# vario_1.net
KiCad netlist of a schematic drawn in EAGLE
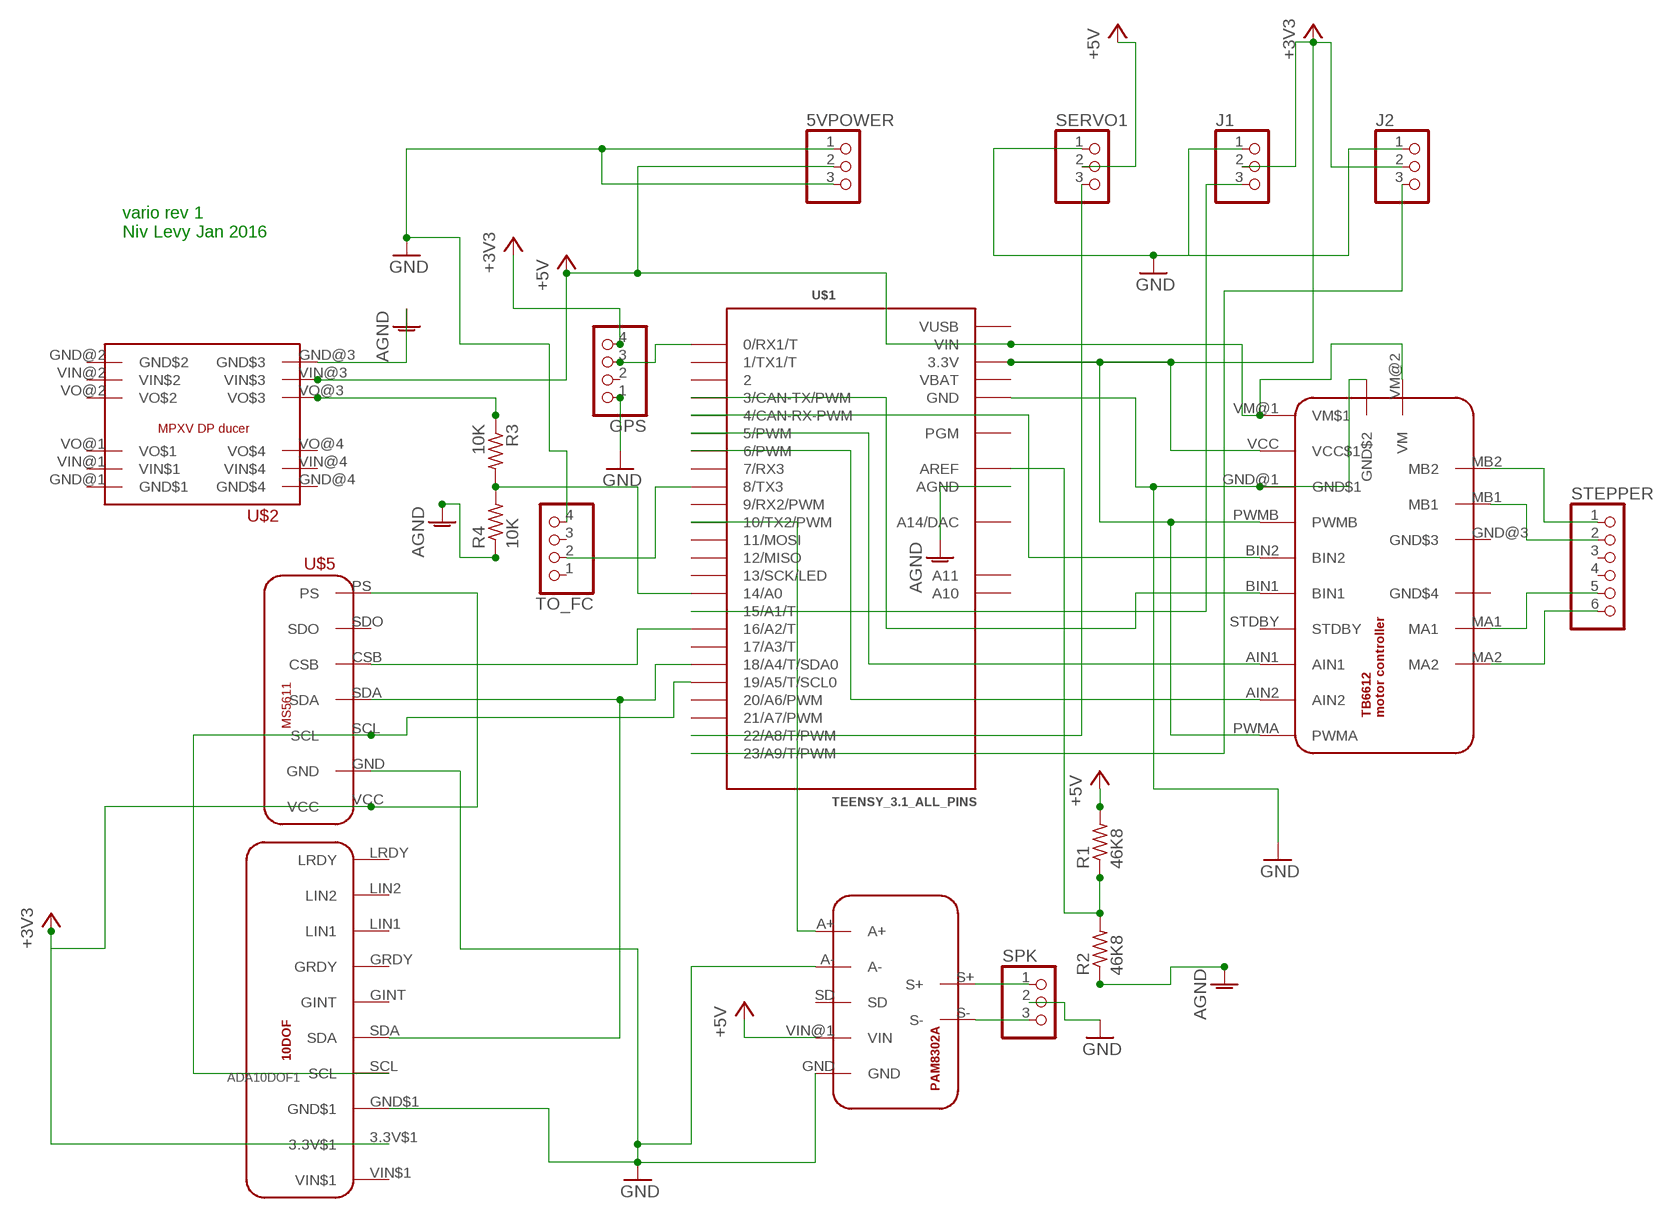
[diagram p0: schematic, sheet 1]

(export (version "E")
  (design (tool "Eeschema 10.0.6"))
  (components
    (comp (ref "5VPOWER")
      (value "PINHD-1X3")
      (footprint "eagle-import:1X03")
      (libsource (lib "eagle-import") (part "PINHD-1X3"))
    )
    (comp (ref "ADA10DOF1")
      (value "10DOF_BREAKOUT")
      (footprint "eagle-import:10_DOF_BREAKOUT")
      (libsource (lib "eagle-import") (part "10DOF_BREAKOUT"))
    )
    (comp (ref "GPS")
      (value "PINHD-1X4")
      (footprint "eagle-import:1X04")
      (libsource (lib "eagle-import") (part "PINHD-1X4"))
    )
    (comp (ref "J1")
      (value "PINHD-1X3")
      (footprint "eagle-import:1X03")
      (libsource (lib "eagle-import") (part "PINHD-1X3"))
    )
    (comp (ref "J2")
      (value "PINHD-1X3")
      (footprint "eagle-import:1X03")
      (libsource (lib "eagle-import") (part "PINHD-1X3"))
    )
    (comp (ref "R1")
      (value "46K8")
      (footprint "eagle-import:0207_10")
      (libsource (lib "eagle-import") (part "R-US_0207/10"))
    )
    (comp (ref "R2")
      (value "46K8")
      (footprint "eagle-import:0207_10")
      (libsource (lib "eagle-import") (part "R-US_0207/10"))
    )
    (comp (ref "R3")
      (value "10K")
      (footprint "eagle-import:0207_10")
      (libsource (lib "eagle-import") (part "R-US_0207/10"))
    )
    (comp (ref "R4")
      (value "10K")
      (footprint "eagle-import:0207_10")
      (libsource (lib "eagle-import") (part "R-US_0207/10"))
    )
    (comp (ref "SERVO1")
      (value "PINHD-1X3")
      (footprint "eagle-import:1X03")
      (libsource (lib "eagle-import") (part "PINHD-1X3"))
    )
    (comp (ref "SPK")
      (value "PINHD-1X3")
      (footprint "eagle-import:1X03")
      (libsource (lib "eagle-import") (part "PINHD-1X3"))
    )
    (comp (ref "STEPPER")
      (value "PINHD-1X6")
      (footprint "eagle-import:1X06")
      (libsource (lib "eagle-import") (part "PINHD-1X6"))
    )
    (comp (ref "TO_FC")
      (value "PINHD-1X4")
      (footprint "eagle-import:1X04")
      (libsource (lib "eagle-import") (part "PINHD-1X4"))
    )
    (comp (ref "U$1")
      (value "TEENSY_3.1_ALL_PINS")
      (footprint "eagle-import:TEENSY3-ALL_PINS")
      (libsource (lib "eagle-import") (part "TEENSY_3.1_ALL_PINS"))
    )
    (comp (ref "U$2")
      (value "MPXV")
      (footprint "eagle-import:MPXV")
      (libsource (lib "eagle-import") (part "MPXV"))
    )
    (comp (ref "U$3")
      (value "TB6612_BREAKOUT")
      (footprint "eagle-import:TB6612_BREAKOUT")
      (libsource (lib "eagle-import") (part "TB6612_BREAKOUT"))
    )
    (comp (ref "U$4")
      (value "PAM8302A_BREAKOUT")
      (footprint "eagle-import:PAM8302A_BREAKOUT")
      (libsource (lib "eagle-import") (part "PAM8302A_BREAKOUT"))
    )
    (comp (ref "U$5")
      (value "MS5611_BREAKOUT")
      (footprint "eagle-import:MS5611_BREAKOUT")
      (libsource (lib "eagle-import") (part "MS5611_BREAKOUT"))
    )
  )
  (nets
    (net (code "1") (name "+3V3") (class "Default")
      (node (ref "ADA10DOF1") (pin "3.3V$1") (pinfunction "3.3V$1_3.3V$1") (pintype "input"))
      (node (ref "GPS") (pin "4") (pinfunction "4_4") (pintype "passive"))
      (node (ref "J1") (pin "2") (pinfunction "2_2") (pintype "passive"))
      (node (ref "J2") (pin "2") (pinfunction "2_2") (pintype "passive"))
      (node (ref "U$1") (pin "3.3V") (pinfunction "3.3V_3.3V") (pintype "power_in"))
      (node (ref "U$1") (pin "3.3V1") (pinfunction "3.3V_3.3V1") (pintype "power_in"))
      (node (ref "U$3") (pin "PWMA") (pinfunction "PWMA_PWMA") (pintype "bidirectional"))
      (node (ref "U$3") (pin "PWMB") (pinfunction "PWMB_PWMB") (pintype "bidirectional"))
      (node (ref "U$3") (pin "VCC") (pinfunction "VCC$1_VCC") (pintype "input"))
      (node (ref "U$5") (pin "PS") (pinfunction "PS_PS") (pintype "bidirectional"))
      (node (ref "U$5") (pin "VCC") (pinfunction "VCC_VCC") (pintype "input"))
    )
    (net (code "2") (name "+5V") (class "Default")
      (node (ref "5VPOWER") (pin "2") (pinfunction "2_2") (pintype "passive"))
      (node (ref "R1") (pin "2") (pinfunction "2_2") (pintype "passive"))
      (node (ref "SERVO1") (pin "2") (pinfunction "2_2") (pintype "passive"))
      (node (ref "U$1") (pin "VIN") (pinfunction "VIN_VIN") (pintype "power_in"))
      (node (ref "U$2") (pin "VIN@3") (pinfunction "VIN$3_VIN@3") (pintype "input"))
      (node (ref "U$3") (pin "VM@1") (pinfunction "VM$1_VM@1") (pintype "input"))
      (node (ref "U$3") (pin "VM@2") (pinfunction "VM_VM@2") (pintype "bidirectional"))
      (node (ref "U$4") (pin "VIN@1") (pinfunction "VIN_VIN@1") (pintype "input"))
    )
    (net (code "3") (name "/VBAT") (class "Default")
      (node (ref "U$1") (pin "VBAT") (pinfunction "VBAT_VBAT") (pintype "power_in"))
    )
    (net (code "4") (name "/VUSB") (class "Default")
      (node (ref "U$1") (pin "VUSB") (pinfunction "VUSB_VUSB") (pintype "power_in"))
    )
    (net (code "5") (name "AGND") (class "Default")
      (node (ref "R2") (pin "1") (pinfunction "1_1") (pintype "passive"))
      (node (ref "R4") (pin "1") (pinfunction "1_1") (pintype "passive"))
      (node (ref "U$1") (pin "AGND") (pinfunction "AGND_AGND") (pintype "power_in"))
      (node (ref "U$2") (pin "GND@3") (pinfunction "GND$3_GND@3") (pintype "input"))
    )
    (net (code "6") (name "GND") (class "Default")
      (node (ref "5VPOWER") (pin "1") (pinfunction "1_1") (pintype "passive"))
      (node (ref "5VPOWER") (pin "3") (pinfunction "3_3") (pintype "passive"))
      (node (ref "ADA10DOF1") (pin "GND$1") (pinfunction "GND$1_GND$1") (pintype "input"))
      (node (ref "GPS") (pin "1") (pinfunction "1_1") (pintype "passive"))
      (node (ref "J1") (pin "1") (pinfunction "1_1") (pintype "passive"))
      (node (ref "J2") (pin "1") (pinfunction "1_1") (pintype "passive"))
      (node (ref "SERVO1") (pin "1") (pinfunction "1_1") (pintype "passive"))
      (node (ref "SPK") (pin "2") (pinfunction "2_2") (pintype "passive"))
      (node (ref "TO_FC") (pin "4") (pinfunction "4_4") (pintype "passive"))
      (node (ref "U$1") (pin "GND") (pinfunction "GND_GND") (pintype "power_in"))
      (node (ref "U$1") (pin "GND1") (pinfunction "GND_GND1") (pintype "power_in"))
      (node (ref "U$3") (pin "GND@1") (pinfunction "GND$1_GND@1") (pintype "input"))
      (node (ref "U$3") (pin "GND@2") (pinfunction "GND$2_GND@2") (pintype "input"))
      (node (ref "U$4") (pin "A-") (pinfunction "A-_A-") (pintype "bidirectional"))
      (node (ref "U$4") (pin "GND") (pinfunction "GND_GND") (pintype "input"))
      (node (ref "U$5") (pin "GND") (pinfunction "GND_GND") (pintype "bidirectional"))
    )
    (net (code "7") (name "Net-(R1-Pad1)") (class "Default")
      (node (ref "R1") (pin "1") (pinfunction "1_1") (pintype "passive"))
      (node (ref "R2") (pin "2") (pinfunction "2_2") (pintype "passive"))
      (node (ref "U$1") (pin "AREF") (pinfunction "AREF_AREF") (pintype "power_in"))
    )
    (net (code "8") (name "Net-(R3-Pad2)") (class "Default")
      (node (ref "R3") (pin "2") (pinfunction "2_2") (pintype "passive"))
      (node (ref "R4") (pin "2") (pinfunction "2_2") (pintype "passive"))
      (node (ref "U$1") (pin "14/A0") (pinfunction "14/A0_14/A0") (pintype "bidirectional"))
    )
    (net (code "9") (name "Net-(SPK-Pad1)") (class "Default")
      (node (ref "SPK") (pin "1") (pinfunction "1_1") (pintype "passive"))
      (node (ref "U$4") (pin "S+") (pinfunction "S+_S+") (pintype "bidirectional"))
    )
    (net (code "10") (name "Net-(SPK-Pad3)") (class "Default")
      (node (ref "SPK") (pin "3") (pinfunction "3_3") (pintype "passive"))
      (node (ref "U$4") (pin "S-") (pinfunction "S-_S-") (pintype "bidirectional"))
    )
    (net (code "11") (name "Net-(STEPPER-Pad1)") (class "Default")
      (node (ref "STEPPER") (pin "1") (pinfunction "1_1") (pintype "passive"))
      (node (ref "U$3") (pin "MB2") (pinfunction "MB2_MB2") (pintype "bidirectional"))
    )
    (net (code "12") (name "Net-(STEPPER-Pad2)") (class "Default")
      (node (ref "STEPPER") (pin "2") (pinfunction "2_2") (pintype "passive"))
      (node (ref "U$3") (pin "MB1") (pinfunction "MB1_MB1") (pintype "bidirectional"))
    )
    (net (code "13") (name "Net-(STEPPER-Pad5)") (class "Default")
      (node (ref "STEPPER") (pin "5") (pinfunction "5_5") (pintype "passive"))
      (node (ref "U$3") (pin "MA1") (pinfunction "MA1_MA1") (pintype "bidirectional"))
    )
    (net (code "14") (name "Net-(STEPPER-Pad6)") (class "Default")
      (node (ref "STEPPER") (pin "6") (pinfunction "6_6") (pintype "passive"))
      (node (ref "U$3") (pin "MA2") (pinfunction "MA2_MA2") (pintype "bidirectional"))
    )
    (net (code "15") (name "Net-(U$1-0{slash}RX1{slash}T)") (class "Default")
      (node (ref "GPS") (pin "3") (pinfunction "3_3") (pintype "passive"))
      (node (ref "U$1") (pin "0") (pinfunction "0/RX1/T_0") (pintype "bidirectional"))
    )
    (net (code "16") (name "Net-(U$1-3{slash}CAN-TX{slash}PWM)") (class "Default")
      (node (ref "U$1") (pin "3") (pinfunction "3/CAN-TX/PWM_3") (pintype "bidirectional"))
      (node (ref "U$3") (pin "BIN1") (pinfunction "BIN1_BIN1") (pintype "bidirectional"))
    )
    (net (code "17") (name "Net-(U$1-4{slash}CAN-RX-PWM)") (class "Default")
      (node (ref "U$1") (pin "4") (pinfunction "4/CAN-RX-PWM_4") (pintype "bidirectional"))
      (node (ref "U$3") (pin "BIN2") (pinfunction "BIN2_BIN2") (pintype "bidirectional"))
    )
    (net (code "18") (name "Net-(U$1-5{slash}PWM)") (class "Default")
      (node (ref "U$1") (pin "5") (pinfunction "5/PWM_5") (pintype "bidirectional"))
      (node (ref "U$3") (pin "AIN1") (pinfunction "AIN1_AIN1") (pintype "bidirectional"))
    )
    (net (code "19") (name "Net-(U$1-6{slash}PWM)") (class "Default")
      (node (ref "U$1") (pin "6") (pinfunction "6/PWM_6") (pintype "bidirectional"))
      (node (ref "U$3") (pin "AIN2") (pinfunction "AIN2_AIN2") (pintype "bidirectional"))
    )
    (net (code "20") (name "Net-(U$1-8{slash}TX3)") (class "Default")
      (node (ref "TO_FC") (pin "2") (pinfunction "2_2") (pintype "passive"))
      (node (ref "U$1") (pin "8") (pinfunction "8/TX3_8") (pintype "bidirectional"))
    )
    (net (code "21") (name "Net-(U$1-10{slash}TX2{slash}PWM)") (class "Default")
      (node (ref "U$1") (pin "10") (pinfunction "10/TX2/PWM_10") (pintype "bidirectional"))
      (node (ref "U$4") (pin "A+") (pinfunction "A+_A+") (pintype "bidirectional"))
    )
    (net (code "22") (name "Net-(U$1-15{slash}A1{slash}T)") (class "Default")
      (node (ref "J1") (pin "3") (pinfunction "3_3") (pintype "passive"))
      (node (ref "U$1") (pin "15/A1") (pinfunction "15/A1/T_15/A1") (pintype "bidirectional"))
    )
    (net (code "23") (name "Net-(U$1-16{slash}A2{slash}T)") (class "Default")
      (node (ref "U$1") (pin "16/A2") (pinfunction "16/A2/T_16/A2") (pintype "bidirectional"))
      (node (ref "U$5") (pin "CSB") (pinfunction "CSB_CSB") (pintype "bidirectional"))
    )
    (net (code "24") (name "Net-(U$1-18{slash}A4{slash}T{slash}SDA0)") (class "Default")
      (node (ref "ADA10DOF1") (pin "SDA") (pinfunction "SDA_SDA") (pintype "bidirectional"))
      (node (ref "U$1") (pin "18/A4") (pinfunction "18/A4/T/SDA0_18/A4") (pintype "bidirectional"))
      (node (ref "U$5") (pin "SDA") (pinfunction "SDA_SDA") (pintype "bidirectional"))
    )
    (net (code "25") (name "Net-(U$1-19{slash}A5{slash}T{slash}SCL0)") (class "Default")
      (node (ref "ADA10DOF1") (pin "SCL") (pinfunction "SCL_SCL") (pintype "bidirectional"))
      (node (ref "U$1") (pin "19/A5") (pinfunction "19/A5/T/SCL0_19/A5") (pintype "bidirectional"))
      (node (ref "U$5") (pin "SCL") (pinfunction "SCL_SCL") (pintype "bidirectional"))
    )
    (net (code "26") (name "Net-(U$1-22{slash}A8{slash}T{slash}PWM)") (class "Default")
      (node (ref "SERVO1") (pin "3") (pinfunction "3_3") (pintype "passive"))
      (node (ref "U$1") (pin "22/A8") (pinfunction "22/A8/T/PWM_22/A8") (pintype "bidirectional"))
    )
    (net (code "27") (name "Net-(U$1-23{slash}A9{slash}T{slash}PWM)") (class "Default")
      (node (ref "J2") (pin "3") (pinfunction "3_3") (pintype "passive"))
      (node (ref "U$1") (pin "23/A9") (pinfunction "23/A9/T/PWM_23/A9") (pintype "bidirectional"))
    )
    (net (code "28") (name "Net-(U$2-VO$3)") (class "Default")
      (node (ref "R3") (pin "1") (pinfunction "1_1") (pintype "passive"))
      (node (ref "U$2") (pin "VO@3") (pinfunction "VO$3_VO@3") (pintype "output"))
    )
    (net (code "29") (name "unconnected-(ADA10DOF1-PadGINT)") (class "Default")
      (node (ref "ADA10DOF1") (pin "GINT") (pinfunction "GINT_GINT") (pintype "bidirectional"))
    )
    (net (code "30") (name "unconnected-(ADA10DOF1-PadGRDY)") (class "Default")
      (node (ref "ADA10DOF1") (pin "GRDY") (pinfunction "GRDY_GRDY") (pintype "bidirectional"))
    )
    (net (code "31") (name "unconnected-(ADA10DOF1-PadLIN1)") (class "Default")
      (node (ref "ADA10DOF1") (pin "LIN1") (pinfunction "LIN1_LIN1") (pintype "bidirectional"))
    )
    (net (code "32") (name "unconnected-(ADA10DOF1-PadLIN2)") (class "Default")
      (node (ref "ADA10DOF1") (pin "LIN2") (pinfunction "LIN2_LIN2") (pintype "bidirectional"))
    )
    (net (code "33") (name "unconnected-(ADA10DOF1-PadLRDY)") (class "Default")
      (node (ref "ADA10DOF1") (pin "LRDY") (pinfunction "LRDY_LRDY") (pintype "bidirectional"))
    )
    (net (code "34") (name "unconnected-(ADA10DOF1-PadVIN$1)") (class "Default")
      (node (ref "ADA10DOF1") (pin "VIN$1") (pinfunction "VIN$1_VIN$1") (pintype "bidirectional"))
    )
    (net (code "35") (name "unconnected-(GPS-Pad2)") (class "Default")
      (node (ref "GPS") (pin "2") (pinfunction "2_2") (pintype "passive"))
    )
    (net (code "36") (name "unconnected-(STEPPER-Pad3)") (class "Default")
      (node (ref "STEPPER") (pin "3") (pinfunction "3_3") (pintype "passive"))
    )
    (net (code "37") (name "unconnected-(STEPPER-Pad4)") (class "Default")
      (node (ref "STEPPER") (pin "4") (pinfunction "4_4") (pintype "passive"))
    )
    (net (code "38") (name "unconnected-(TO_FC-Pad1)") (class "Default")
      (node (ref "TO_FC") (pin "1") (pinfunction "1_1") (pintype "passive"))
    )
    (net (code "39") (name "unconnected-(TO_FC-Pad3)") (class "Default")
      (node (ref "TO_FC") (pin "3") (pinfunction "3_3") (pintype "passive"))
    )
    (net (code "40") (name "unconnected-(U$1-1{slash}TX1{slash}T-Pad1)") (class "Default")
      (node (ref "U$1") (pin "1") (pinfunction "1/TX1/T_1") (pintype "bidirectional"))
    )
    (net (code "41") (name "unconnected-(U$1-7{slash}RX3-Pad7)") (class "Default")
      (node (ref "U$1") (pin "7") (pinfunction "7/RX3_7") (pintype "bidirectional"))
    )
    (net (code "42") (name "unconnected-(U$1-9{slash}RX2{slash}PWM-Pad9)") (class "Default")
      (node (ref "U$1") (pin "9") (pinfunction "9/RX2/PWM_9") (pintype "bidirectional"))
    )
    (net (code "43") (name "unconnected-(U$1-11{slash}MOSI-Pad11)") (class "Default")
      (node (ref "U$1") (pin "11") (pinfunction "11/MOSI_11") (pintype "bidirectional"))
    )
    (net (code "44") (name "unconnected-(U$1-12{slash}MISO-Pad12)") (class "Default")
      (node (ref "U$1") (pin "12") (pinfunction "12/MISO_12") (pintype "bidirectional"))
    )
    (net (code "45") (name "unconnected-(U$1-13{slash}SCK{slash}LED-Pad13)") (class "Default")
      (node (ref "U$1") (pin "13") (pinfunction "13/SCK/LED_13") (pintype "bidirectional"))
    )
    (net (code "46") (name "unconnected-(U$1-17{slash}A3{slash}T-Pad17{slash}A3)") (class "Default")
      (node (ref "U$1") (pin "17/A3") (pinfunction "17/A3/T_17/A3") (pintype "bidirectional"))
    )
    (net (code "47") (name "unconnected-(U$1-20{slash}A6{slash}PWM-Pad20{slash}A6)") (class "Default")
      (node (ref "U$1") (pin "20/A6") (pinfunction "20/A6/PWM_20/A6") (pintype "bidirectional"))
    )
    (net (code "48") (name "unconnected-(U$1-21{slash}A7{slash}PWM-Pad21{slash}A7)") (class "Default")
      (node (ref "U$1") (pin "21/A7") (pinfunction "21/A7/PWM_21/A7") (pintype "bidirectional"))
    )
    (net (code "49") (name "unconnected-(U$1-A14{slash}DAC-PadRESET{slash}DAC)") (class "Default")
      (node (ref "U$1") (pin "RESET/DAC") (pinfunction "A14/DAC_RESET/DAC") (pintype "bidirectional"))
    )
    (net (code "50") (name "unconnected-(U$1-Pad2)") (class "Default")
      (node (ref "U$1") (pin "2") (pinfunction "2_2") (pintype "bidirectional"))
    )
    (net (code "51") (name "unconnected-(U$1-PadA10)") (class "Default")
      (node (ref "U$1") (pin "A10") (pinfunction "A10_A10") (pintype "bidirectional"))
    )
    (net (code "52") (name "unconnected-(U$1-PadA11)") (class "Default")
      (node (ref "U$1") (pin "A11") (pinfunction "A11_A11") (pintype "bidirectional"))
    )
    (net (code "53") (name "unconnected-(U$1-PadPGM)") (class "Default")
      (node (ref "U$1") (pin "PGM") (pinfunction "PGM_PGM") (pintype "bidirectional"))
    )
    (net (code "54") (name "unconnected-(U$2-GND$1-PadGND@1)") (class "Default")
      (node (ref "U$2") (pin "GND@1") (pinfunction "GND$1_GND@1") (pintype "input"))
    )
    (net (code "55") (name "unconnected-(U$2-GND$2-PadGND@2)") (class "Default")
      (node (ref "U$2") (pin "GND@2") (pinfunction "GND$2_GND@2") (pintype "input"))
    )
    (net (code "56") (name "unconnected-(U$2-GND$4-PadGND@4)") (class "Default")
      (node (ref "U$2") (pin "GND@4") (pinfunction "GND$4_GND@4") (pintype "input"))
    )
    (net (code "57") (name "unconnected-(U$2-VIN$1-PadVIN@1)") (class "Default")
      (node (ref "U$2") (pin "VIN@1") (pinfunction "VIN$1_VIN@1") (pintype "input"))
    )
    (net (code "58") (name "unconnected-(U$2-VIN$2-PadVIN@2)") (class "Default")
      (node (ref "U$2") (pin "VIN@2") (pinfunction "VIN$2_VIN@2") (pintype "input"))
    )
    (net (code "59") (name "unconnected-(U$2-VIN$4-PadVIN@4)") (class "Default")
      (node (ref "U$2") (pin "VIN@4") (pinfunction "VIN$4_VIN@4") (pintype "bidirectional"))
    )
    (net (code "60") (name "unconnected-(U$2-VO$1-PadVO@1)") (class "Default")
      (node (ref "U$2") (pin "VO@1") (pinfunction "VO$1_VO@1") (pintype "output"))
    )
    (net (code "61") (name "unconnected-(U$2-VO$2-PadVO@2)") (class "Default")
      (node (ref "U$2") (pin "VO@2") (pinfunction "VO$2_VO@2") (pintype "output"))
    )
    (net (code "62") (name "unconnected-(U$2-VO$4-PadVO@4)") (class "Default")
      (node (ref "U$2") (pin "VO@4") (pinfunction "VO$4_VO@4") (pintype "output"))
    )
    (net (code "63") (name "unconnected-(U$3-GND$3-PadGND@3)") (class "Default")
      (node (ref "U$3") (pin "GND@3") (pinfunction "GND$3_GND@3") (pintype "input"))
    )
    (net (code "64") (name "unconnected-(U$3-GND$4-PadGND@4)") (class "Default")
      (node (ref "U$3") (pin "GND@4") (pinfunction "GND$4_GND@4") (pintype "input"))
    )
    (net (code "65") (name "unconnected-(U$3-PadSTDBY)") (class "Default")
      (node (ref "U$3") (pin "STDBY") (pinfunction "STDBY_STDBY") (pintype "bidirectional"))
    )
    (net (code "66") (name "unconnected-(U$4-PadSD)") (class "Default")
      (node (ref "U$4") (pin "SD") (pinfunction "SD_SD") (pintype "bidirectional"))
    )
    (net (code "67") (name "unconnected-(U$5-PadSDO)") (class "Default")
      (node (ref "U$5") (pin "SDO") (pinfunction "SDO_SDO") (pintype "bidirectional"))
    )
  )
)
